# BuckConverter.net
KiCad netlist of a schematic drawn in Altium Designer
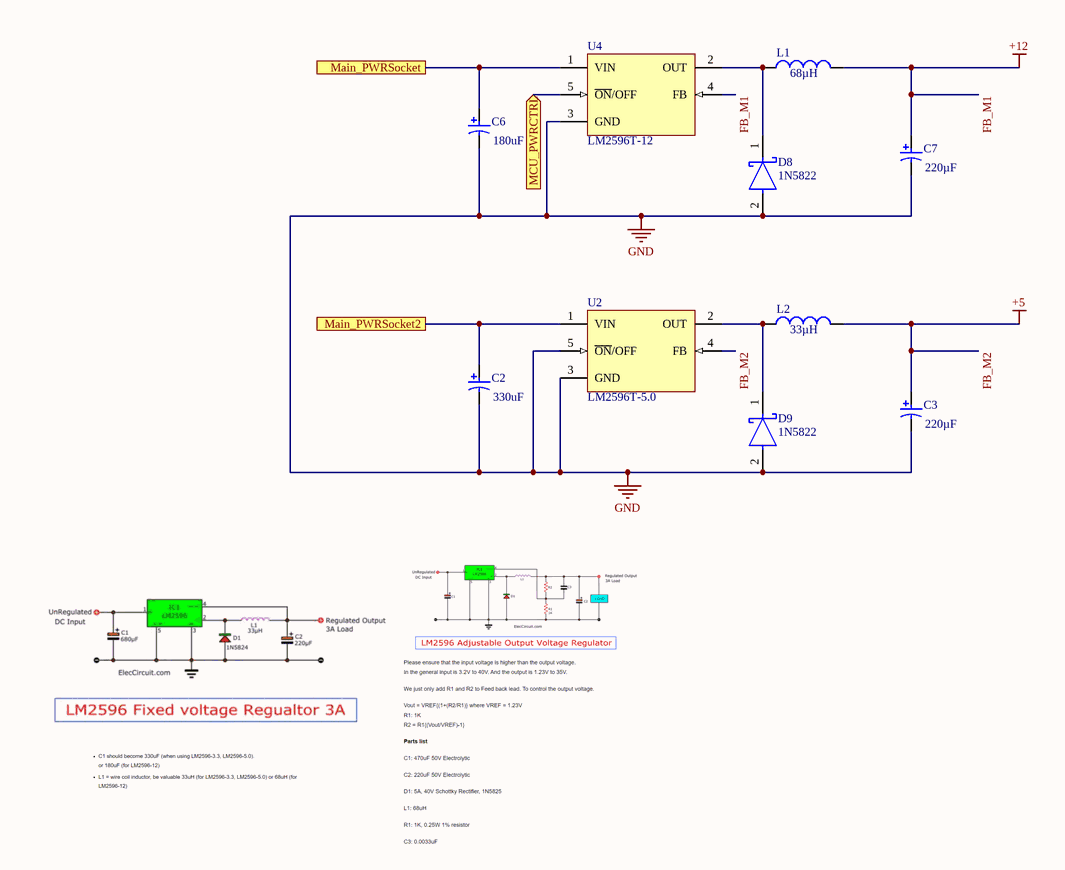
[diagram p0: BuckConverter.SchDoc]

(export (version "E")
  (design (tool "Eeschema 10.0.6"))
  (components
    (comp (ref "C2")
      (value "16SVP180MX")
      (footprint "PNSC-SVP-F8_L")
      (fields
        (field (name "VOLTAGE") "16VDC")
        (field (name "CAPACITANCE") "330uF")
        (field (name "MANUFACTURER") "Panasonic")
      )
      (libsource (lib "Altium Content Vault") (part "CAP-P-2"))
    )
    (comp (ref "C3")
      (value "EEU-FM1H221")
      (footprint "PNSC-EEUFM1H221-2")
      (description "Radial Lead Aluminum Electrolytic Capacitor, 220 uF, +/- 20%, 50 V, -40 to 105 degC, RoHS, Bulk")
      (fields (field (name "MANUFACTURER") "Panasonic") (field (name "CAPACITANCE") "220µF"))
      (libsource (lib "Altium Content Vault") (part "CAP-P-2"))
    )
    (comp (ref "C6")
      (value "16SVP180MX")
      (footprint "PNSC-SVP-F8_L")
      (fields
        (field (name "VOLTAGE") "16VDC")
        (field (name "CAPACITANCE") "180uF")
        (field (name "MANUFACTURER") "Panasonic")
      )
      (libsource (lib "Altium Content Vault") (part "CAP-P-2"))
    )
    (comp (ref "C7")
      (value "EEU-FM1H221")
      (footprint "PNSC-EEUFM1H221-2")
      (description "Radial Lead Aluminum Electrolytic Capacitor, 220 uF, +/- 20%, 50 V, -40 to 105 degC, RoHS, Bulk")
      (fields (field (name "MANUFACTURER") "Panasonic") (field (name "CAPACITANCE") "220µF"))
      (libsource (lib "Altium Content Vault") (part "CAP-P-2"))
    )
    (comp (ref "D8")
      (value "1N5822")
      (footprint "FP-DO-201AD-MFG")
      (description "DIODE SCHOTTKY 40V 3A DO201AD")
      (fields
        (field (name "OCTOPART") "https://octopart.com/1n5822-stmicroelectronics-323225")
        (field (name "MANUFACTURER") "STMicroelectronics")
      )
      (libsource (lib "Altium Content Vault") (part "1d6ec82d83fb6aee721767c19dac4b9"))
    )
    (comp (ref "D9")
      (value "1N5822")
      (footprint "FP-DO-201AD-MFG")
      (description "DIODE SCHOTTKY 40V 3A DO201AD")
      (fields
        (field (name "OCTOPART") "https://octopart.com/1n5822-stmicroelectronics-323225")
        (field (name "MANUFACTURER") "STMicroelectronics")
      )
      (libsource (lib "Altium Content Vault") (part "1d6ec82d83fb6aee721767c19dac4b9"))
    )
    (comp (ref "L1")
      (value "AIAP-03-220K")
      (footprint "CAPA81-2290X1140_V")
      (description "Axial Power Inductor, 22 uH, +/- 10%, -55 to 125 degC, 2-Pin THD, RoHS, Bulk")
      (fields
        (field (name "INDUCTANCE") "68µH")
        (field (name "MANUFACTURER") "Abracon")
        (field (name "TOLERANCE") "±10%")
      )
      (libsource (lib "Altium Content Vault") (part "IND-2"))
    )
    (comp (ref "L2")
      (value "AIAP-03-220K")
      (footprint "CAPA81-2290X1140_V")
      (description "Axial Power Inductor, 22 uH, +/- 10%, -55 to 125 degC, 2-Pin THD, RoHS, Bulk")
      (fields
        (field (name "INDUCTANCE") "33µH")
        (field (name "MANUFACTURER") "Abracon")
        (field (name "TOLERANCE") "±10%")
      )
      (libsource (lib "Altium Content Vault") (part "IND-2"))
    )
    (comp (ref "U2")
      (value "LM2596T-5.0")
      (footprint "NDH0005A")
      (description "SIMPLE SWITCHER® Power Converter 150 KHz 3A Step-Down Voltage Regulator, 5-pin TO-220")
      (fields (field (name "MANUFACTURER") "Texas Instruments"))
      (libsource (lib "Altium Content Vault") (part "PM-REG-LM2575HVT-12"))
    )
    (comp (ref "U4")
      (value "LM2596T-12")
      (footprint "T05D")
      (description "SIMPLE SWITCHER® Power Converter 150 KHz 3A Step-Down Voltage Regulator, 5-pin TO-220")
      (fields (field (name "MANUFACTURER") "National Semiconductor"))
      (libsource (lib "Altium Content Vault") (part "PM-REG-LM2575HVT-12"))
    )
  )
  (nets
    (net (code "1") (name "+5") (class "Default")
      (node (ref "C3") (pin "1") (pinfunction "1_1") (pintype "passive"))
      (node (ref "L2") (pin "2") (pinfunction "2_2") (pintype "passive"))
      (node (ref "U2") (pin "4") (pinfunction "FB_4") (pintype "input"))
    )
    (net (code "2") (name "+12") (class "Default")
      (node (ref "C7") (pin "1") (pinfunction "1_1") (pintype "passive"))
      (node (ref "L1") (pin "2") (pinfunction "2_2") (pintype "passive"))
      (node (ref "U4") (pin "4") (pinfunction "FB_4") (pintype "input"))
    )
    (net (code "3") (name "/MCU_PWRCTRL") (class "Default")
      (node (ref "U4") (pin "5") (pinfunction "~{ON}/OFF_5") (pintype "input"))
    )
    (net (code "4") (name "/Main_PWRSocket") (class "Default")
      (node (ref "C6") (pin "1") (pinfunction "1_1") (pintype "passive"))
      (node (ref "U4") (pin "1") (pinfunction "VIN_1") (pintype "power_in"))
    )
    (net (code "5") (name "/Main_PWRSocket2") (class "Default")
      (node (ref "C2") (pin "1") (pinfunction "1_1") (pintype "passive"))
      (node (ref "U2") (pin "1") (pinfunction "VIN_1") (pintype "power_in"))
    )
    (net (code "6") (name "GND") (class "Default")
      (node (ref "C2") (pin "2") (pinfunction "2_2") (pintype "passive"))
      (node (ref "C3") (pin "2") (pinfunction "2_2") (pintype "passive"))
      (node (ref "C6") (pin "2") (pinfunction "2_2") (pintype "passive"))
      (node (ref "C7") (pin "2") (pinfunction "2_2") (pintype "passive"))
      (node (ref "D8") (pin "2") (pinfunction "A_2") (pintype "passive"))
      (node (ref "D9") (pin "2") (pinfunction "A_2") (pintype "passive"))
      (node (ref "U2") (pin "3") (pinfunction "GND_3") (pintype "power_in"))
      (node (ref "U2") (pin "5") (pinfunction "~{ON}/OFF_5") (pintype "input"))
      (node (ref "U4") (pin "3") (pinfunction "GND_3") (pintype "power_in"))
    )
    (net (code "7") (name "Net-(D8-C)") (class "Default")
      (node (ref "D8") (pin "1") (pinfunction "C_1") (pintype "passive"))
      (node (ref "L1") (pin "1") (pinfunction "1_1") (pintype "passive"))
      (node (ref "U4") (pin "2") (pinfunction "OUT_2") (pintype "power_in"))
    )
    (net (code "8") (name "Net-(D9-C)") (class "Default")
      (node (ref "D9") (pin "1") (pinfunction "C_1") (pintype "passive"))
      (node (ref "L2") (pin "1") (pinfunction "1_1") (pintype "passive"))
      (node (ref "U2") (pin "2") (pinfunction "OUT_2") (pintype "power_in"))
    )
  )
)
